# MicroHDMI_D-Type_Dummy_Plug.net
KiCad netlist of a schematic drawn in EasyEDA Pro
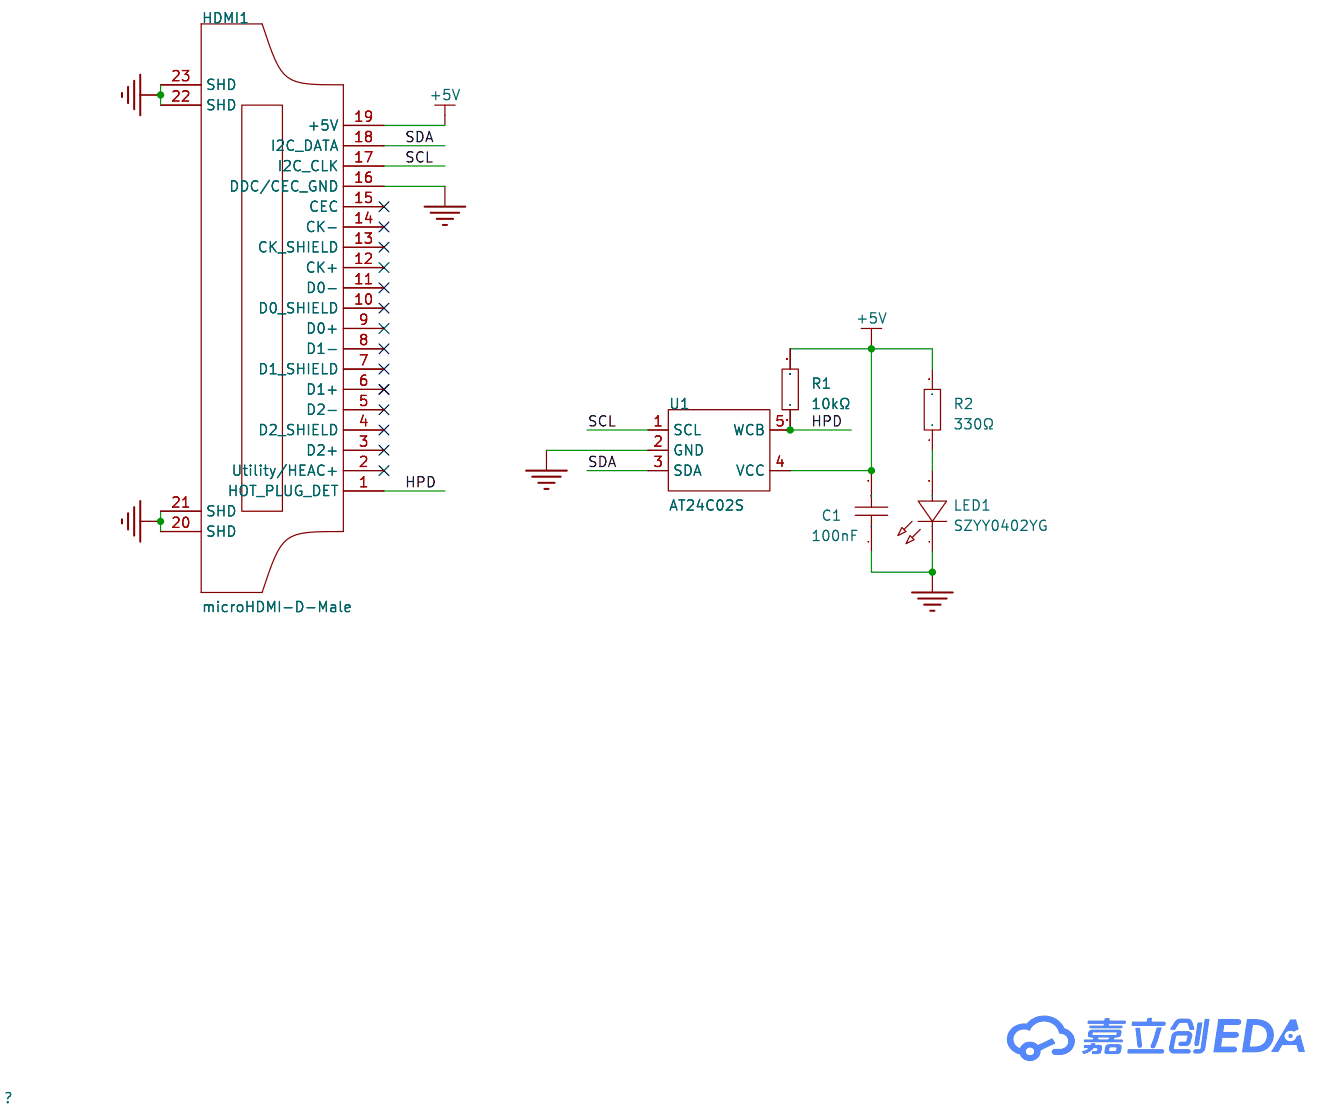
[diagram p0: schematic sheet]

(export (version "E")
  (design (tool "Eeschema 10.0.6"))
  (components
    (comp (ref "C1")
      (value "100nF")
      (footprint "easyedapro:C0402")
      (description "容值:100nF;精度:±10%;额定电压:16V;温度系数:X7R;")
      (fields
        (field (name "Manufacturer Part") "CL05B104KO5NNNC")
        (field (name "Manufacturer") "SAMSUNG(三星)")
      )
      (libsource (lib "easyedapro") (part "CL05B104KO5NNNC"))
    )
    (comp (ref "HDMI1")
      (value "microHDMI-D-Male")
      (footprint "easyedapro:HDIM-SMD_HDMI-D-Male")
      (description "夹板0.9镀金 2.1版本支持8k高清")
      (fields (field (name "Manufacturer") "None"))
      (libsource (lib "easyedapro") (part "microHDMI-D-Male"))
    )
    (comp (ref "LED1")
      (value "SZYY0402YG")
      (footprint "easyedapro:LED0402-RD_GREEN")
      (description "发光颜色:黄绿色;")
      (fields (field (name "Manufacturer") "yongyu(永裕光电)"))
      (libsource (lib "easyedapro") (part "SZYY0402YG"))
    )
    (comp (ref "R1")
      (value "10kΩ")
      (footprint "easyedapro:R0402")
      (description "电阻类型:厚膜电阻;阻值:10kΩ;精度:±1%;功率:62.5mW;工作电压:50V;温度系数:±100ppm/°C;")
      (fields
        (field (name "Manufacturer Part") "0402WGF1002TCE")
        (field (name "Manufacturer") "UNI-ROYAL(厚声)")
      )
      (libsource (lib "easyedapro") (part "0402WGF1002TCE"))
    )
    (comp (ref "R2")
      (value "330Ω")
      (footprint "easyedapro:R0402")
      (description "电阻类型:厚膜电阻;阻值:330Ω;精度:±1%;功率:62.5mW;工作电压:50V;温度系数:±100ppm/°C;")
      (fields
        (field (name "Manufacturer Part") "0402WGF3300TCE")
        (field (name "Manufacturer") "UNI-ROYAL(厚声)")
      )
      (libsource (lib "easyedapro") (part "0402WGF3300TCE"))
    )
    (comp (ref "U1")
      (value "AT24C02S")
      (footprint "easyedapro:SOT-23-5_L3.0-W1.7-P0.95-LS2.8-BL")
      (description "接口类型:I2C;存储容量:2Kbit;时钟频率(fc):1MHz;")
      (fields (field (name "Manufacturer") "TDSEMIC(拓电半导体)"))
      (libsource (lib "easyedapro") (part "AT24C02S"))
    )
  )
  (nets
    (net (code "1") (name "+5V") (class "Default")
      (node (ref "C1") (pin "2") (pinfunction "2_2") (pintype "unspecified"))
      (node (ref "HDMI1") (pin "19") (pinfunction "+5V_19") (pintype "unspecified"))
      (node (ref "R1") (pin "2") (pinfunction "2_2") (pintype "input"))
      (node (ref "R2") (pin "2") (pinfunction "2_2") (pintype "input"))
      (node (ref "U1") (pin "4") (pinfunction "VCC_4") (pintype "unspecified"))
    )
    (net (code "2") (name "/HPD") (class "Default")
      (node (ref "HDMI1") (pin "1") (pinfunction "HOT_PLUG_DET_1") (pintype "unspecified"))
      (node (ref "R1") (pin "1") (pinfunction "1_1") (pintype "input"))
      (node (ref "U1") (pin "5") (pinfunction "WCB_5") (pintype "unspecified"))
    )
    (net (code "3") (name "/SCL") (class "Default")
      (node (ref "HDMI1") (pin "17") (pinfunction "I2C_CLK_17") (pintype "unspecified"))
      (node (ref "U1") (pin "1") (pinfunction "SCL_1") (pintype "unspecified"))
    )
    (net (code "4") (name "/SDA") (class "Default")
      (node (ref "HDMI1") (pin "18") (pinfunction "I2C_DATA_18") (pintype "unspecified"))
      (node (ref "U1") (pin "3") (pinfunction "SDA_3") (pintype "unspecified"))
    )
    (net (code "5") (name "GND") (class "Default")
      (node (ref "C1") (pin "1") (pinfunction "1_1") (pintype "unspecified"))
      (node (ref "HDMI1") (pin "16") (pinfunction "DDC/CEC_GND_16") (pintype "unspecified"))
      (node (ref "HDMI1") (pin "20") (pinfunction "SHD_20") (pintype "unspecified"))
      (node (ref "HDMI1") (pin "21") (pinfunction "SHD_21") (pintype "unspecified"))
      (node (ref "HDMI1") (pin "22") (pinfunction "SHD_22") (pintype "unspecified"))
      (node (ref "HDMI1") (pin "23") (pinfunction "SHD_23") (pintype "unspecified"))
      (node (ref "LED1") (pin "1") (pinfunction "K_1") (pintype "unspecified"))
      (node (ref "U1") (pin "2") (pinfunction "GND_2") (pintype "unspecified"))
    )
    (net (code "6") (name "Net-(LED1-A)") (class "Default")
      (node (ref "LED1") (pin "2") (pinfunction "A_2") (pintype "unspecified"))
      (node (ref "R2") (pin "1") (pinfunction "1_1") (pintype "input"))
    )
    (net (code "7") (name "unconnected-(HDMI1-CEC-Pad15)") (class "Default")
      (node (ref "HDMI1") (pin "15") (pinfunction "CEC_15") (pintype "unspecified+no_connect"))
    )
    (net (code "8") (name "unconnected-(HDMI1-CK+-Pad12)") (class "Default")
      (node (ref "HDMI1") (pin "12") (pinfunction "CK+_12") (pintype "unspecified+no_connect"))
    )
    (net (code "9") (name "unconnected-(HDMI1-CK--Pad14)") (class "Default")
      (node (ref "HDMI1") (pin "14") (pinfunction "CK-_14") (pintype "unspecified+no_connect"))
    )
    (net (code "10") (name "unconnected-(HDMI1-CK_SHIELD-Pad13)") (class "Default")
      (node (ref "HDMI1") (pin "13") (pinfunction "CK_SHIELD_13") (pintype "unspecified+no_connect"))
    )
    (net (code "11") (name "unconnected-(HDMI1-D0+-Pad9)") (class "Default")
      (node (ref "HDMI1") (pin "9") (pinfunction "D0+_9") (pintype "unspecified+no_connect"))
    )
    (net (code "12") (name "unconnected-(HDMI1-D0--Pad11)") (class "Default")
      (node (ref "HDMI1") (pin "11") (pinfunction "D0-_11") (pintype "unspecified+no_connect"))
    )
    (net (code "13") (name "unconnected-(HDMI1-D0_SHIELD-Pad10)") (class "Default")
      (node (ref "HDMI1") (pin "10") (pinfunction "D0_SHIELD_10") (pintype "unspecified+no_connect"))
    )
    (net (code "14") (name "unconnected-(HDMI1-D1+-Pad6)") (class "Default")
      (node (ref "HDMI1") (pin "6") (pinfunction "D1+_6") (pintype "unspecified+no_connect"))
    )
    (net (code "15") (name "unconnected-(HDMI1-D1--Pad8)") (class "Default")
      (node (ref "HDMI1") (pin "8") (pinfunction "D1-_8") (pintype "unspecified+no_connect"))
    )
    (net (code "16") (name "unconnected-(HDMI1-D1_SHIELD-Pad7)") (class "Default")
      (node (ref "HDMI1") (pin "7") (pinfunction "D1_SHIELD_7") (pintype "unspecified+no_connect"))
    )
    (net (code "17") (name "unconnected-(HDMI1-D2+-Pad3)") (class "Default")
      (node (ref "HDMI1") (pin "3") (pinfunction "D2+_3") (pintype "unspecified+no_connect"))
    )
    (net (code "18") (name "unconnected-(HDMI1-D2--Pad5)") (class "Default")
      (node (ref "HDMI1") (pin "5") (pinfunction "D2-_5") (pintype "unspecified+no_connect"))
    )
    (net (code "19") (name "unconnected-(HDMI1-D2_SHIELD-Pad4)") (class "Default")
      (node (ref "HDMI1") (pin "4") (pinfunction "D2_SHIELD_4") (pintype "unspecified+no_connect"))
    )
    (net (code "20") (name "unconnected-(HDMI1-Utility{slash}HEAC+-Pad2)") (class "Default")
      (node (ref "HDMI1") (pin "2") (pinfunction "Utility/HEAC+_2") (pintype "unspecified+no_connect"))
    )
  )
)
